# led_driver_board.net
KiCad netlist of a schematic drawn in EAGLE
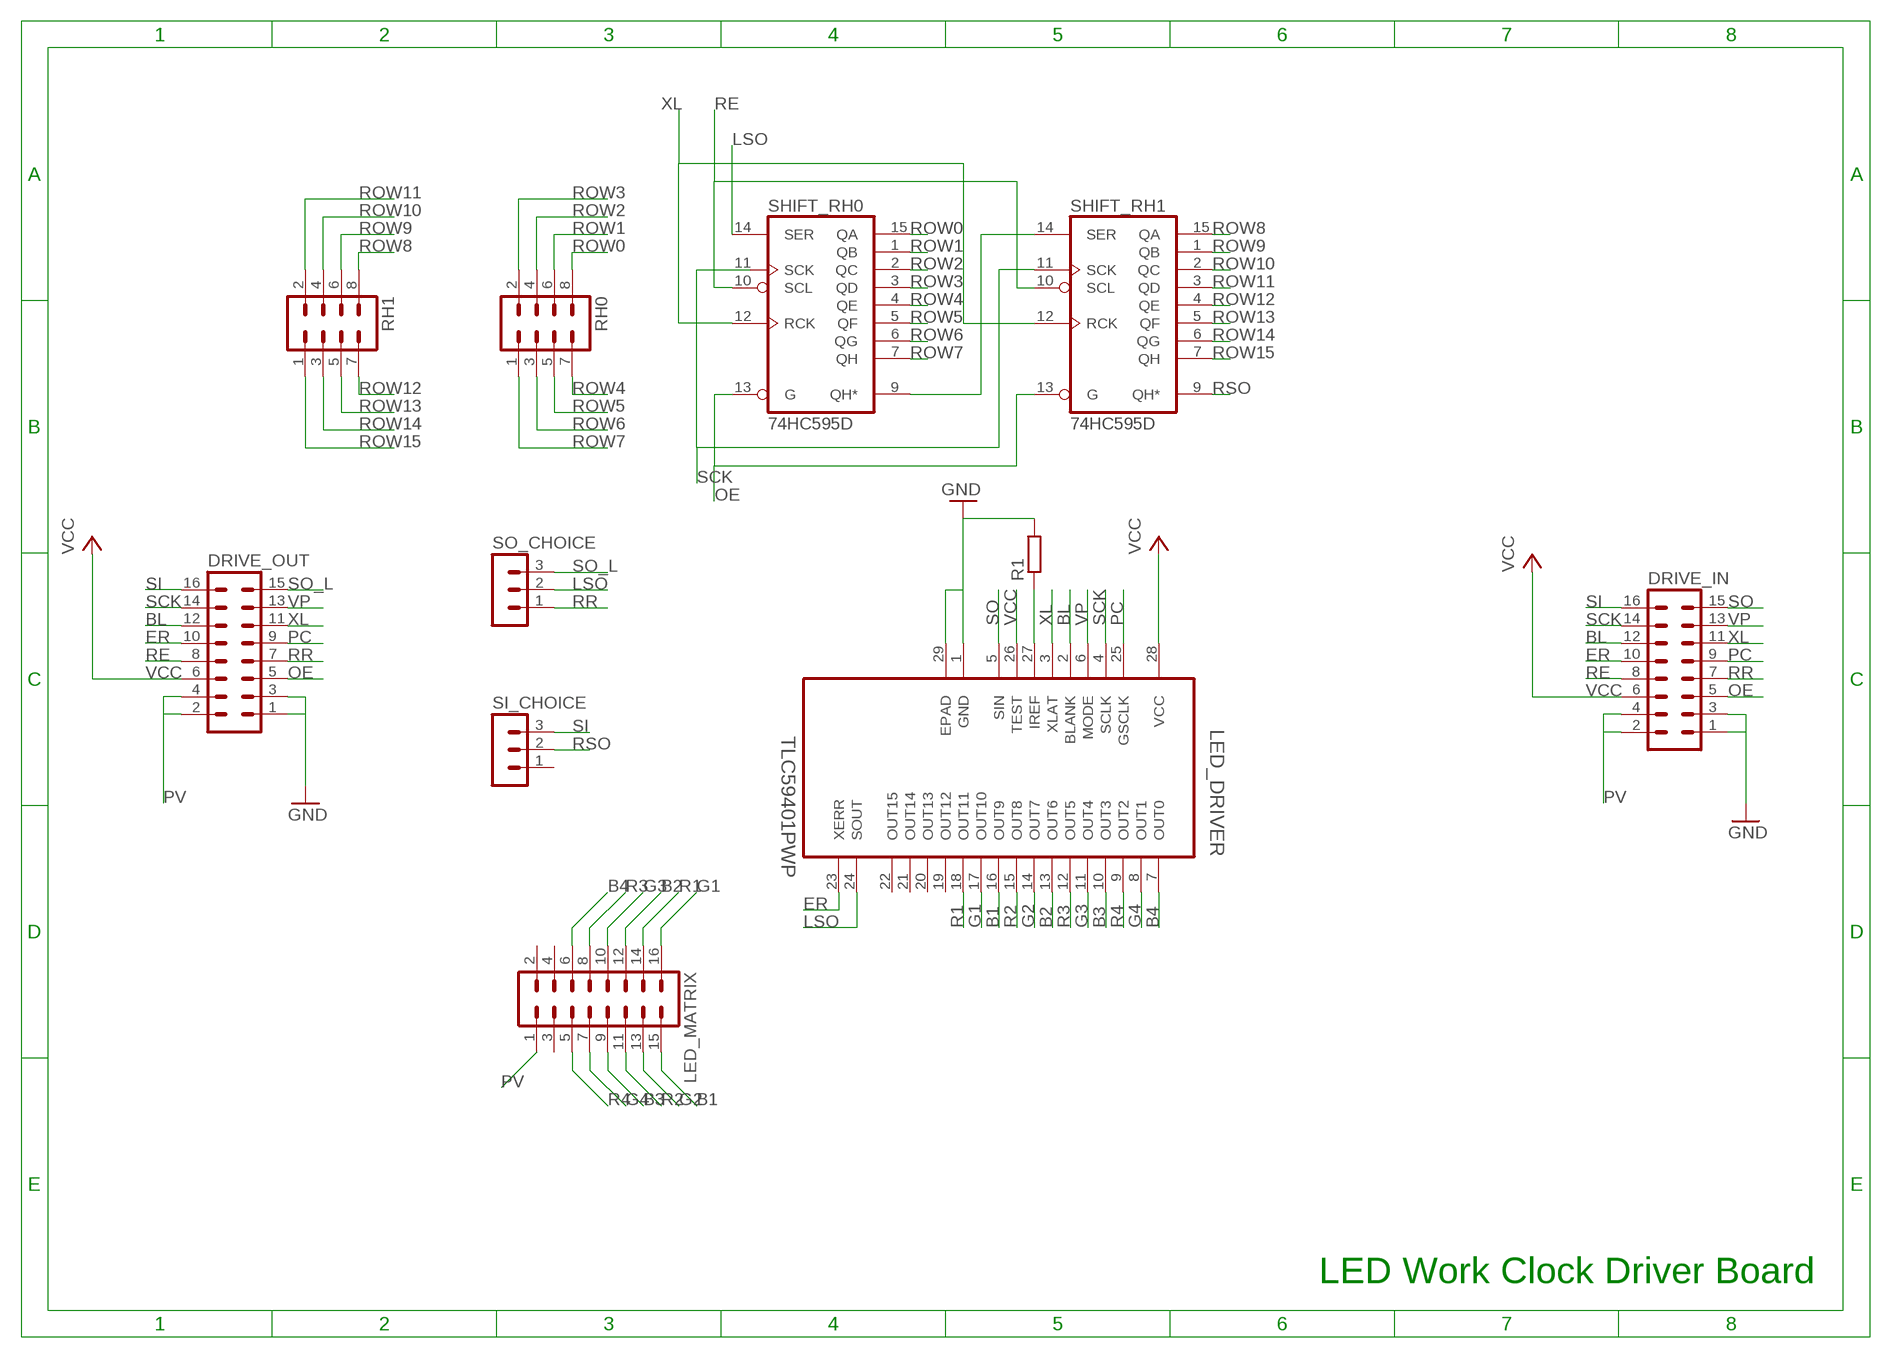
[diagram p0: schematic, sheet 1]

(export (version "E")
  (design (tool "Eeschema 10.0.6"))
  (components
    (comp (ref "DRIVE_IN")
      (value "MA08-2")
      (footprint "eagle-import:MA08-2")
      (libsource (lib "eagle-import") (part "MA08-2"))
    )
    (comp (ref "DRIVE_OUT")
      (value "MA08-2")
      (footprint "eagle-import:MA08-2")
      (libsource (lib "eagle-import") (part "MA08-2"))
    )
    (comp (ref "LED_DRIVER")
      (value "TLC59401PWP")
      (footprint "eagle-import:SOP65P640X120-29N")
      (libsource (lib "eagle-import") (part "TLC59401PWP"))
    )
    (comp (ref "LED_MATRIX")
      (value "MA08-2")
      (footprint "eagle-import:MA08-2")
      (libsource (lib "eagle-import") (part "MA08-2"))
    )
    (comp (ref "R1")
      (value "R-EU_0204/7")
      (footprint "eagle-import:0204_7")
      (libsource (lib "eagle-import") (part "R-EU_0204/7"))
    )
    (comp (ref "RH0")
      (value "MA04-2")
      (footprint "eagle-import:MA04-2")
      (libsource (lib "eagle-import") (part "MA04-2"))
    )
    (comp (ref "RH1")
      (value "MA04-2")
      (footprint "eagle-import:MA04-2")
      (libsource (lib "eagle-import") (part "MA04-2"))
    )
    (comp (ref "SHIFT_RH0")
      (value "74HC595D")
      (footprint "eagle-import:SO16")
      (libsource (lib "eagle-import") (part "74595DHC"))
    )
    (comp (ref "SHIFT_RH1")
      (value "74HC595D")
      (footprint "eagle-import:SO16")
      (libsource (lib "eagle-import") (part "74595DHC"))
    )
    (comp (ref "SI_CHOICE")
      (value "MA03-1")
      (footprint "eagle-import:MA03-1")
      (libsource (lib "eagle-import") (part "MA03-1"))
    )
    (comp (ref "SO_CHOICE")
      (value "MA03-1")
      (footprint "eagle-import:MA03-1")
      (libsource (lib "eagle-import") (part "MA03-1"))
    )
  )
  (nets
    (net (code "1") (name "/B1") (class "Default")
      (node (ref "LED_DRIVER") (pin "16") (pinfunction "OUT9_16") (pintype "output"))
      (node (ref "LED_MATRIX") (pin "15") (pinfunction "15_15") (pintype "passive"))
    )
    (net (code "2") (name "/B2") (class "Default")
      (node (ref "LED_DRIVER") (pin "13") (pinfunction "OUT6_13") (pintype "output"))
      (node (ref "LED_MATRIX") (pin "12") (pinfunction "12_12") (pintype "passive"))
    )
    (net (code "3") (name "/B3") (class "Default")
      (node (ref "LED_DRIVER") (pin "10") (pinfunction "OUT3_10") (pintype "output"))
      (node (ref "LED_MATRIX") (pin "9") (pinfunction "9_9") (pintype "passive"))
    )
    (net (code "4") (name "/B4") (class "Default")
      (node (ref "LED_DRIVER") (pin "7") (pinfunction "OUT0_7") (pintype "output"))
      (node (ref "LED_MATRIX") (pin "6") (pinfunction "6_6") (pintype "passive"))
    )
    (net (code "5") (name "/BL") (class "Default")
      (node (ref "DRIVE_IN") (pin "12") (pinfunction "12_12") (pintype "passive"))
      (node (ref "DRIVE_OUT") (pin "12") (pinfunction "12_12") (pintype "passive"))
      (node (ref "LED_DRIVER") (pin "2") (pinfunction "BLANK_2") (pintype "input"))
    )
    (net (code "6") (name "/ER") (class "Default")
      (node (ref "DRIVE_IN") (pin "10") (pinfunction "10_10") (pintype "passive"))
      (node (ref "DRIVE_OUT") (pin "10") (pinfunction "10_10") (pintype "passive"))
      (node (ref "LED_DRIVER") (pin "23") (pinfunction "XERR_23") (pintype "output"))
    )
    (net (code "7") (name "/G1") (class "Default")
      (node (ref "LED_DRIVER") (pin "17") (pinfunction "OUT10_17") (pintype "output"))
      (node (ref "LED_MATRIX") (pin "16") (pinfunction "16_16") (pintype "passive"))
    )
    (net (code "8") (name "/G2") (class "Default")
      (node (ref "LED_DRIVER") (pin "14") (pinfunction "OUT7_14") (pintype "output"))
      (node (ref "LED_MATRIX") (pin "13") (pinfunction "13_13") (pintype "passive"))
    )
    (net (code "9") (name "/G3") (class "Default")
      (node (ref "LED_DRIVER") (pin "11") (pinfunction "OUT4_11") (pintype "output"))
      (node (ref "LED_MATRIX") (pin "10") (pinfunction "10_10") (pintype "passive"))
    )
    (net (code "10") (name "/G4") (class "Default")
      (node (ref "LED_DRIVER") (pin "8") (pinfunction "OUT1_8") (pintype "output"))
      (node (ref "LED_MATRIX") (pin "7") (pinfunction "7_7") (pintype "passive"))
    )
    (net (code "11") (name "/LSO") (class "Default")
      (node (ref "LED_DRIVER") (pin "24") (pinfunction "SOUT_24") (pintype "output"))
      (node (ref "SHIFT_RH0") (pin "14") (pinfunction "SER_14") (pintype "input"))
      (node (ref "SO_CHOICE") (pin "2") (pinfunction "2_2") (pintype "passive"))
    )
    (net (code "12") (name "/OE") (class "Default")
      (node (ref "DRIVE_IN") (pin "5") (pinfunction "5_5") (pintype "passive"))
      (node (ref "DRIVE_OUT") (pin "5") (pinfunction "5_5") (pintype "passive"))
      (node (ref "SHIFT_RH0") (pin "13") (pinfunction "G_13") (pintype "input"))
      (node (ref "SHIFT_RH1") (pin "13") (pinfunction "G_13") (pintype "input"))
    )
    (net (code "13") (name "/PC") (class "Default")
      (node (ref "DRIVE_IN") (pin "9") (pinfunction "9_9") (pintype "passive"))
      (node (ref "DRIVE_OUT") (pin "9") (pinfunction "9_9") (pintype "passive"))
      (node (ref "LED_DRIVER") (pin "25") (pinfunction "GSCLK_25") (pintype "input"))
    )
    (net (code "14") (name "/PV") (class "Default")
      (node (ref "DRIVE_IN") (pin "2") (pinfunction "2_2") (pintype "passive"))
      (node (ref "DRIVE_IN") (pin "4") (pinfunction "4_4") (pintype "passive"))
      (node (ref "DRIVE_OUT") (pin "2") (pinfunction "2_2") (pintype "passive"))
      (node (ref "DRIVE_OUT") (pin "4") (pinfunction "4_4") (pintype "passive"))
      (node (ref "LED_MATRIX") (pin "1") (pinfunction "1_1") (pintype "passive"))
    )
    (net (code "15") (name "/R1") (class "Default")
      (node (ref "LED_DRIVER") (pin "18") (pinfunction "OUT11_18") (pintype "output"))
      (node (ref "LED_MATRIX") (pin "14") (pinfunction "14_14") (pintype "passive"))
    )
    (net (code "16") (name "/R2") (class "Default")
      (node (ref "LED_DRIVER") (pin "15") (pinfunction "OUT8_15") (pintype "output"))
      (node (ref "LED_MATRIX") (pin "11") (pinfunction "11_11") (pintype "passive"))
    )
    (net (code "17") (name "/R3") (class "Default")
      (node (ref "LED_DRIVER") (pin "12") (pinfunction "OUT5_12") (pintype "output"))
      (node (ref "LED_MATRIX") (pin "8") (pinfunction "8_8") (pintype "passive"))
    )
    (net (code "18") (name "/R4") (class "Default")
      (node (ref "LED_DRIVER") (pin "9") (pinfunction "OUT2_9") (pintype "output"))
      (node (ref "LED_MATRIX") (pin "5") (pinfunction "5_5") (pintype "passive"))
    )
    (net (code "19") (name "/RE") (class "Default")
      (node (ref "DRIVE_IN") (pin "8") (pinfunction "8_8") (pintype "passive"))
      (node (ref "DRIVE_OUT") (pin "8") (pinfunction "8_8") (pintype "passive"))
      (node (ref "SHIFT_RH0") (pin "10") (pinfunction "SCL_10") (pintype "input"))
      (node (ref "SHIFT_RH1") (pin "10") (pinfunction "SCL_10") (pintype "input"))
    )
    (net (code "20") (name "/ROW0") (class "Default")
      (node (ref "RH0") (pin "8") (pinfunction "8_8") (pintype "passive"))
      (node (ref "SHIFT_RH0") (pin "15") (pinfunction "QA_15") (pintype "tri_state"))
    )
    (net (code "21") (name "/ROW1") (class "Default")
      (node (ref "RH0") (pin "6") (pinfunction "6_6") (pintype "passive"))
      (node (ref "SHIFT_RH0") (pin "1") (pinfunction "QB_1") (pintype "tri_state"))
    )
    (net (code "22") (name "/ROW2") (class "Default")
      (node (ref "RH0") (pin "4") (pinfunction "4_4") (pintype "passive"))
      (node (ref "SHIFT_RH0") (pin "2") (pinfunction "QC_2") (pintype "tri_state"))
    )
    (net (code "23") (name "/ROW3") (class "Default")
      (node (ref "RH0") (pin "2") (pinfunction "2_2") (pintype "passive"))
      (node (ref "SHIFT_RH0") (pin "3") (pinfunction "QD_3") (pintype "tri_state"))
    )
    (net (code "24") (name "/ROW4") (class "Default")
      (node (ref "RH0") (pin "7") (pinfunction "7_7") (pintype "passive"))
      (node (ref "SHIFT_RH0") (pin "4") (pinfunction "QE_4") (pintype "tri_state"))
    )
    (net (code "25") (name "/ROW5") (class "Default")
      (node (ref "RH0") (pin "5") (pinfunction "5_5") (pintype "passive"))
      (node (ref "SHIFT_RH0") (pin "5") (pinfunction "QF_5") (pintype "tri_state"))
    )
    (net (code "26") (name "/ROW6") (class "Default")
      (node (ref "RH0") (pin "3") (pinfunction "3_3") (pintype "passive"))
      (node (ref "SHIFT_RH0") (pin "6") (pinfunction "QG_6") (pintype "tri_state"))
    )
    (net (code "27") (name "/ROW7") (class "Default")
      (node (ref "RH0") (pin "1") (pinfunction "1_1") (pintype "passive"))
      (node (ref "SHIFT_RH0") (pin "7") (pinfunction "QH_7") (pintype "tri_state"))
    )
    (net (code "28") (name "/ROW8") (class "Default")
      (node (ref "RH1") (pin "8") (pinfunction "8_8") (pintype "passive"))
      (node (ref "SHIFT_RH1") (pin "15") (pinfunction "QA_15") (pintype "tri_state"))
    )
    (net (code "29") (name "/ROW9") (class "Default")
      (node (ref "RH1") (pin "6") (pinfunction "6_6") (pintype "passive"))
      (node (ref "SHIFT_RH1") (pin "1") (pinfunction "QB_1") (pintype "tri_state"))
    )
    (net (code "30") (name "/ROW10") (class "Default")
      (node (ref "RH1") (pin "4") (pinfunction "4_4") (pintype "passive"))
      (node (ref "SHIFT_RH1") (pin "2") (pinfunction "QC_2") (pintype "tri_state"))
    )
    (net (code "31") (name "/ROW11") (class "Default")
      (node (ref "RH1") (pin "2") (pinfunction "2_2") (pintype "passive"))
      (node (ref "SHIFT_RH1") (pin "3") (pinfunction "QD_3") (pintype "tri_state"))
    )
    (net (code "32") (name "/ROW12") (class "Default")
      (node (ref "RH1") (pin "7") (pinfunction "7_7") (pintype "passive"))
      (node (ref "SHIFT_RH1") (pin "4") (pinfunction "QE_4") (pintype "tri_state"))
    )
    (net (code "33") (name "/ROW13") (class "Default")
      (node (ref "RH1") (pin "5") (pinfunction "5_5") (pintype "passive"))
      (node (ref "SHIFT_RH1") (pin "5") (pinfunction "QF_5") (pintype "tri_state"))
    )
    (net (code "34") (name "/ROW14") (class "Default")
      (node (ref "RH1") (pin "3") (pinfunction "3_3") (pintype "passive"))
      (node (ref "SHIFT_RH1") (pin "6") (pinfunction "QG_6") (pintype "tri_state"))
    )
    (net (code "35") (name "/ROW15") (class "Default")
      (node (ref "RH1") (pin "1") (pinfunction "1_1") (pintype "passive"))
      (node (ref "SHIFT_RH1") (pin "7") (pinfunction "QH_7") (pintype "tri_state"))
    )
    (net (code "36") (name "/RR") (class "Default")
      (node (ref "DRIVE_IN") (pin "7") (pinfunction "7_7") (pintype "passive"))
      (node (ref "DRIVE_OUT") (pin "7") (pinfunction "7_7") (pintype "passive"))
      (node (ref "SO_CHOICE") (pin "1") (pinfunction "1_1") (pintype "passive"))
    )
    (net (code "37") (name "/RSO") (class "Default")
      (node (ref "SHIFT_RH1") (pin "9") (pinfunction "QH*_9") (pintype "tri_state"))
      (node (ref "SI_CHOICE") (pin "2") (pinfunction "2_2") (pintype "passive"))
    )
    (net (code "38") (name "/SCK") (class "Default")
      (node (ref "DRIVE_IN") (pin "14") (pinfunction "14_14") (pintype "passive"))
      (node (ref "DRIVE_OUT") (pin "14") (pinfunction "14_14") (pintype "passive"))
      (node (ref "LED_DRIVER") (pin "4") (pinfunction "SCLK_4") (pintype "input"))
      (node (ref "SHIFT_RH0") (pin "11") (pinfunction "SCK_11") (pintype "input"))
      (node (ref "SHIFT_RH1") (pin "11") (pinfunction "SCK_11") (pintype "input"))
    )
    (net (code "39") (name "/SI") (class "Default")
      (node (ref "DRIVE_IN") (pin "16") (pinfunction "16_16") (pintype "passive"))
      (node (ref "DRIVE_OUT") (pin "16") (pinfunction "16_16") (pintype "passive"))
      (node (ref "SI_CHOICE") (pin "3") (pinfunction "3_3") (pintype "passive"))
    )
    (net (code "40") (name "/SO") (class "Default")
      (node (ref "DRIVE_IN") (pin "15") (pinfunction "15_15") (pintype "passive"))
      (node (ref "LED_DRIVER") (pin "5") (pinfunction "SIN_5") (pintype "input"))
    )
    (net (code "41") (name "/SO_L") (class "Default")
      (node (ref "DRIVE_OUT") (pin "15") (pinfunction "15_15") (pintype "passive"))
      (node (ref "SO_CHOICE") (pin "3") (pinfunction "3_3") (pintype "passive"))
    )
    (net (code "42") (name "/VP") (class "Default")
      (node (ref "DRIVE_IN") (pin "13") (pinfunction "13_13") (pintype "passive"))
      (node (ref "DRIVE_OUT") (pin "13") (pinfunction "13_13") (pintype "passive"))
      (node (ref "LED_DRIVER") (pin "6") (pinfunction "MODE_6") (pintype "input"))
    )
    (net (code "43") (name "/XL") (class "Default")
      (node (ref "DRIVE_IN") (pin "11") (pinfunction "11_11") (pintype "passive"))
      (node (ref "DRIVE_OUT") (pin "11") (pinfunction "11_11") (pintype "passive"))
      (node (ref "LED_DRIVER") (pin "3") (pinfunction "XLAT_3") (pintype "input"))
      (node (ref "SHIFT_RH0") (pin "12") (pinfunction "RCK_12") (pintype "input"))
      (node (ref "SHIFT_RH1") (pin "12") (pinfunction "RCK_12") (pintype "input"))
    )
    (net (code "44") (name "GND") (class "Default")
      (node (ref "DRIVE_IN") (pin "1") (pinfunction "1_1") (pintype "passive"))
      (node (ref "DRIVE_IN") (pin "3") (pinfunction "3_3") (pintype "passive"))
      (node (ref "DRIVE_OUT") (pin "1") (pinfunction "1_1") (pintype "passive"))
      (node (ref "DRIVE_OUT") (pin "3") (pinfunction "3_3") (pintype "passive"))
      (node (ref "LED_DRIVER") (pin "1") (pinfunction "GND_1") (pintype "passive"))
      (node (ref "LED_DRIVER") (pin "29") (pinfunction "EPAD_29") (pintype "passive"))
      (node (ref "R1") (pin "2") (pinfunction "2_2") (pintype "passive"))
    )
    (net (code "45") (name "Net-(LED_DRIVER-IREF)") (class "Default")
      (node (ref "LED_DRIVER") (pin "27") (pinfunction "IREF_27") (pintype "input"))
      (node (ref "R1") (pin "1") (pinfunction "1_1") (pintype "passive"))
    )
    (net (code "46") (name "Net-(SHIFT_RH0A-QH*)") (class "Default")
      (node (ref "SHIFT_RH0") (pin "9") (pinfunction "QH*_9") (pintype "tri_state"))
      (node (ref "SHIFT_RH1") (pin "14") (pinfunction "SER_14") (pintype "input"))
    )
    (net (code "47") (name "VCC") (class "Default")
      (node (ref "DRIVE_IN") (pin "6") (pinfunction "6_6") (pintype "passive"))
      (node (ref "DRIVE_OUT") (pin "6") (pinfunction "6_6") (pintype "passive"))
      (node (ref "LED_DRIVER") (pin "26") (pinfunction "TEST_26") (pintype "input"))
      (node (ref "LED_DRIVER") (pin "28") (pinfunction "VCC_28") (pintype "power_in"))
    )
    (net (code "48") (name "unconnected-(LED_DRIVER-OUT12-Pad19)") (class "Default")
      (node (ref "LED_DRIVER") (pin "19") (pinfunction "OUT12_19") (pintype "output"))
    )
    (net (code "49") (name "unconnected-(LED_DRIVER-OUT13-Pad20)") (class "Default")
      (node (ref "LED_DRIVER") (pin "20") (pinfunction "OUT13_20") (pintype "output"))
    )
    (net (code "50") (name "unconnected-(LED_DRIVER-OUT14-Pad21)") (class "Default")
      (node (ref "LED_DRIVER") (pin "21") (pinfunction "OUT14_21") (pintype "output"))
    )
    (net (code "51") (name "unconnected-(LED_DRIVER-OUT15-Pad22)") (class "Default")
      (node (ref "LED_DRIVER") (pin "22") (pinfunction "OUT15_22") (pintype "output"))
    )
    (net (code "52") (name "unconnected-(LED_MATRIX-Pad2)") (class "Default")
      (node (ref "LED_MATRIX") (pin "2") (pinfunction "2_2") (pintype "passive"))
    )
    (net (code "53") (name "unconnected-(LED_MATRIX-Pad3)") (class "Default")
      (node (ref "LED_MATRIX") (pin "3") (pinfunction "3_3") (pintype "passive"))
    )
    (net (code "54") (name "unconnected-(LED_MATRIX-Pad4)") (class "Default")
      (node (ref "LED_MATRIX") (pin "4") (pinfunction "4_4") (pintype "passive"))
    )
    (net (code "55") (name "unconnected-(SI_CHOICE-Pad1)") (class "Default")
      (node (ref "SI_CHOICE") (pin "1") (pinfunction "1_1") (pintype "passive"))
    )
  )
)
